# BMS-BQ76930.net
KiCad netlist of a schematic drawn in Altium Designer
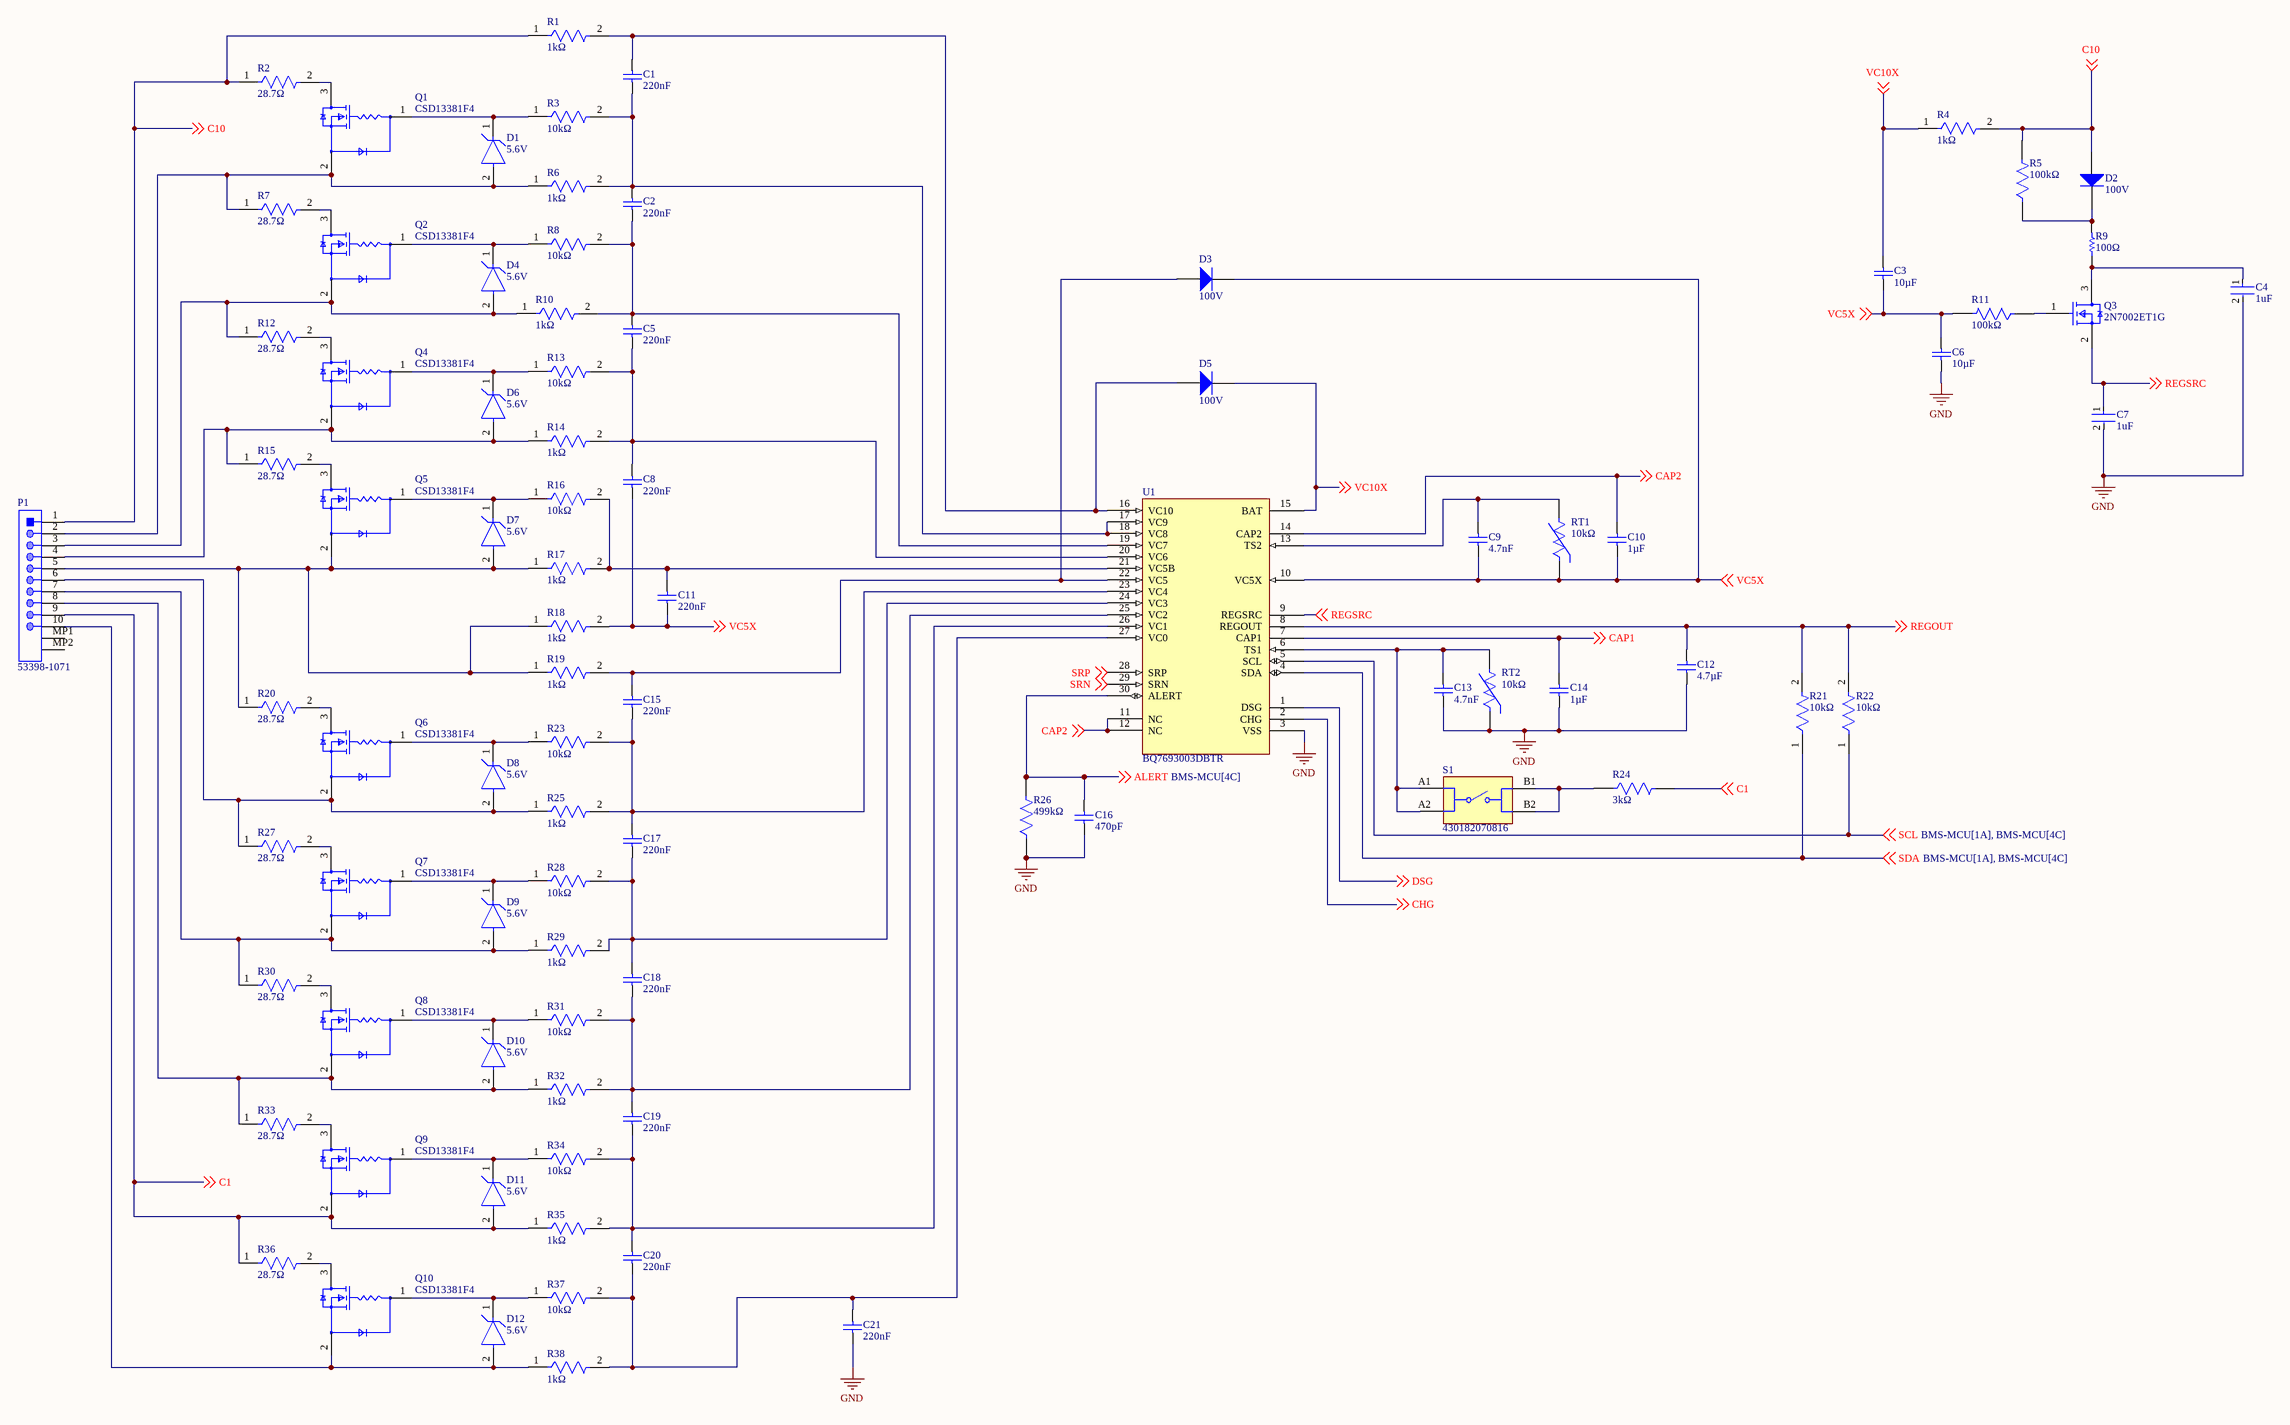
[diagram p0: BMS-BQ76930.SchDoc]

(export (version "E")
  (design (tool "Eeschema 10.0.6"))
  (components
    (comp (ref "C1")
      (value "885012206048")
      (footprint "WCAP-CSGP_0603_L1.6W0.8H0.8_Reflow")
      (description "885012206048 Ceramic Capacitor 220nF, 16VDC, 0603, ±10 %")
      (fields (field (name "TOLERANCE") "10%") (field (name "CAPACITANCE") "220nF"))
      (libsource (lib "BMS-lib") (part "CMP-03913-53914757-1"))
    )
    (comp (ref "C2")
      (value "885012206048")
      (footprint "WCAP-CSGP_0603_L1.6W0.8H0.8_Reflow")
      (description "885012206048 Ceramic Capacitor 220nF, 16VDC, 0603, ±10 %")
      (fields (field (name "TOLERANCE") "10%") (field (name "CAPACITANCE") "220nF"))
      (libsource (lib "BMS-lib") (part "CMP-03913-53914757-1"))
    )
    (comp (ref "C3")
      (value "GRM32ER7YA106KA12L")
      (footprint "CAPC3225X270X30ML30")
      (description "Chip Capacitor, 10 uF, +/- 10%, 35 V, -55 to 125 degC, 1210 (3225 Metric), RoHS, Tape and Reel")
      (fields (field (name "MANUFACTURER") "Murata") (field (name "CAPACITANCE") "10µF"))
      (libsource (lib "BMS-lib") (part "CMP-1038-02234-2"))
    )
    (comp (ref "C4")
      (value "GCJ21BR71H105KA01L")
      (footprint "FP-GCJ21B-0_3-IPC_B")
      (description "Multilayer Ceramic Capacitors MLCC - SMD/SMT 0805 1uF 10%, 50VDC,  X7R 15%")
      (fields (field (name "TOLERANCE") "10%") (field (name "CAPACITANCE") "1uF"))
      (libsource (lib "BMS-lib") (part "CMP-06035-043290-1"))
    )
    (comp (ref "C5")
      (value "885012206048")
      (footprint "WCAP-CSGP_0603_L1.6W0.8H0.8_Reflow")
      (description "885012206048 Ceramic Capacitor 220nF, 16VDC, 0603, ±10 %")
      (fields (field (name "TOLERANCE") "10%") (field (name "CAPACITANCE") "220nF"))
      (libsource (lib "BMS-lib") (part "CMP-03913-53914757-1"))
    )
    (comp (ref "C6")
      (value "GRM32ER7YA106KA12L")
      (footprint "CAPC3225X270X30ML30")
      (description "Chip Capacitor, 10 uF, +/- 10%, 35 V, -55 to 125 degC, 1210 (3225 Metric), RoHS, Tape and Reel")
      (fields (field (name "MANUFACTURER") "Murata") (field (name "CAPACITANCE") "10µF"))
      (libsource (lib "BMS-lib") (part "CMP-1038-02234-2"))
    )
    (comp (ref "C7")
      (value "GCJ21BR71H105KA01L")
      (footprint "FP-GCJ21B-0_3-IPC_B")
      (description "Multilayer Ceramic Capacitors MLCC - SMD/SMT 0805 1uF 10%, 50VDC,  X7R 15%")
      (fields (field (name "TOLERANCE") "10%") (field (name "CAPACITANCE") "1uF"))
      (libsource (lib "BMS-lib") (part "CMP-06035-043290-1"))
    )
    (comp (ref "C8")
      (value "885012206048")
      (footprint "WCAP-CSGP_0603_L1.6W0.8H0.8_Reflow")
      (description "885012206048 Ceramic Capacitor 220nF, 16VDC, 0603, ±10 %")
      (fields (field (name "TOLERANCE") "10%") (field (name "CAPACITANCE") "220nF"))
      (libsource (lib "BMS-lib") (part "CMP-03913-53914757-1"))
    )
    (comp (ref "C9")
      (value "885012206087")
      (footprint "WCAP-CSGP_0603_L1.6W0.8H0.8_Reflow")
      (description "885012206087 Cap Cer 4700PF 50V X7R 0603")
      (fields (field (name "TOLERANCE") "10%") (field (name "CAPACITANCE") "4.7nF"))
      (libsource (lib "BMS-lib") (part "CMP-03913-53914796-1"))
    )
    (comp (ref "C10")
      (value "885012206052")
      (footprint "WCAP-CSGP_0603_L1.6W0.8H0.8_Reflow")
      (fields (field (name "TOLERANCE") "10%") (field (name "CAPACITANCE") "1µF"))
      (libsource (lib "BMS-lib") (part "CMP-03913-53914761-1"))
    )
    (comp (ref "C11")
      (value "885012206048")
      (footprint "WCAP-CSGP_0603_L1.6W0.8H0.8_Reflow")
      (description "885012206048 Ceramic Capacitor 220nF, 16VDC, 0603, ±10 %")
      (fields (field (name "TOLERANCE") "10%") (field (name "CAPACITANCE") "220nF"))
      (libsource (lib "BMS-lib") (part "CMP-03913-53914757-1"))
    )
    (comp (ref "C12")
      (value "885012207025")
      (footprint "WCAP-CSGP_0805_L2W1.25H1.25")
      (fields (field (name "TOLERANCE") "10%") (field (name "CAPACITANCE") "4.7µF"))
      (libsource (lib "BMS-lib") (part "CMP-03913-65419799-1"))
    )
    (comp (ref "C13")
      (value "885012206087")
      (footprint "WCAP-CSGP_0603_L1.6W0.8H0.8_Reflow")
      (description "885012206087 Cap Cer 4700PF 50V X7R 0603")
      (fields (field (name "TOLERANCE") "10%") (field (name "CAPACITANCE") "4.7nF"))
      (libsource (lib "BMS-lib") (part "CMP-03913-53914796-1"))
    )
    (comp (ref "C14")
      (value "885012206052")
      (footprint "WCAP-CSGP_0603_L1.6W0.8H0.8_Reflow")
      (fields (field (name "TOLERANCE") "10%") (field (name "CAPACITANCE") "1µF"))
      (libsource (lib "BMS-lib") (part "CMP-03913-53914761-1"))
    )
    (comp (ref "C15")
      (value "885012206048")
      (footprint "WCAP-CSGP_0603_L1.6W0.8H0.8_Reflow")
      (description "885012206048 Ceramic Capacitor 220nF, 16VDC, 0603, ±10 %")
      (fields (field (name "TOLERANCE") "10%") (field (name "CAPACITANCE") "220nF"))
      (libsource (lib "BMS-lib") (part "CMP-03913-53914757-1"))
    )
    (comp (ref "C16")
      (value "885012206081")
      (footprint "WCAP-CSGP_0603_L1.6W0.8H0.8_Reflow")
      (description "885012206081 Cap Cer 470PF 50V X7R 0603")
      (fields (field (name "TOLERANCE") "10%") (field (name "CAPACITANCE") "470pF"))
      (libsource (lib "BMS-lib") (part "CMP-03913-53914790-1"))
    )
    (comp (ref "C17")
      (value "885012206048")
      (footprint "WCAP-CSGP_0603_L1.6W0.8H0.8_Reflow")
      (description "885012206048 Ceramic Capacitor 220nF, 16VDC, 0603, ±10 %")
      (fields (field (name "TOLERANCE") "10%") (field (name "CAPACITANCE") "220nF"))
      (libsource (lib "BMS-lib") (part "CMP-03913-53914757-1"))
    )
    (comp (ref "C18")
      (value "885012206048")
      (footprint "WCAP-CSGP_0603_L1.6W0.8H0.8_Reflow")
      (description "885012206048 Ceramic Capacitor 220nF, 16VDC, 0603, ±10 %")
      (fields (field (name "TOLERANCE") "10%") (field (name "CAPACITANCE") "220nF"))
      (libsource (lib "BMS-lib") (part "CMP-03913-53914757-1"))
    )
    (comp (ref "C19")
      (value "885012206048")
      (footprint "WCAP-CSGP_0603_L1.6W0.8H0.8_Reflow")
      (description "885012206048 Ceramic Capacitor 220nF, 16VDC, 0603, ±10 %")
      (fields (field (name "TOLERANCE") "10%") (field (name "CAPACITANCE") "220nF"))
      (libsource (lib "BMS-lib") (part "CMP-03913-53914757-1"))
    )
    (comp (ref "C20")
      (value "885012206048")
      (footprint "WCAP-CSGP_0603_L1.6W0.8H0.8_Reflow")
      (description "885012206048 Ceramic Capacitor 220nF, 16VDC, 0603, ±10 %")
      (fields (field (name "TOLERANCE") "10%") (field (name "CAPACITANCE") "220nF"))
      (libsource (lib "BMS-lib") (part "CMP-03913-53914757-1"))
    )
    (comp (ref "C21")
      (value "885012206048")
      (footprint "WCAP-CSGP_0603_L1.6W0.8H0.8_Reflow")
      (description "885012206048 Ceramic Capacitor 220nF, 16VDC, 0603, ±10 %")
      (fields (field (name "TOLERANCE") "10%") (field (name "CAPACITANCE") "220nF"))
      (libsource (lib "BMS-lib") (part "CMP-03913-53914757-1"))
    )
    (comp (ref "D1")
      (value "MM3Z5V6ST1G")
      (footprint "FP-477-02-MFG")
      (description "DIODE ZENER 5.6V 300MW SOD323")
      (fields (field (name "TOLERANCE") "2%") (field (name "VOLTAGE RATING (DC)") "5.6V"))
      (libsource (lib "BMS-lib") (part "CMP-1060-00706-2"))
    )
    (comp (ref "D2")
      (value "1N4148W-7-F")
      (footprint "DIOD-SOD123-2_V")
      (description "Fast Switching Diode, 100 V, 0.15 A, -65 to 150 degC, 2-Pin?SOD123, RoHS, Tape and Reel")
      (fields (field (name "MANUFACTURER") "DiodesIncorporated") (field (name "PEAK REVERSE VOLTAGE") "100V"))
      (libsource (lib "BMS-lib") (part "CMP-2000-04932-2"))
    )
    (comp (ref "D3")
      (value "1N4148W-7-F")
      (footprint "DIOD-SOD123-2_V")
      (description "Fast Switching Diode, 100 V, 0.15 A, -65 to 150 degC, 2-Pin?SOD123, RoHS, Tape and Reel")
      (fields (field (name "MANUFACTURER") "DiodesIncorporated") (field (name "PEAK REVERSE VOLTAGE") "100V"))
      (libsource (lib "BMS-lib") (part "CMP-2000-04932-2"))
    )
    (comp (ref "D4")
      (value "MM3Z5V6ST1G")
      (footprint "FP-477-02-MFG")
      (description "DIODE ZENER 5.6V 300MW SOD323")
      (fields (field (name "TOLERANCE") "2%") (field (name "VOLTAGE RATING (DC)") "5.6V"))
      (libsource (lib "BMS-lib") (part "CMP-1060-00706-2"))
    )
    (comp (ref "D5")
      (value "1N4148W-7-F")
      (footprint "DIOD-SOD123-2_V")
      (description "Fast Switching Diode, 100 V, 0.15 A, -65 to 150 degC, 2-Pin?SOD123, RoHS, Tape and Reel")
      (fields (field (name "MANUFACTURER") "DiodesIncorporated") (field (name "PEAK REVERSE VOLTAGE") "100V"))
      (libsource (lib "BMS-lib") (part "CMP-2000-04932-2"))
    )
    (comp (ref "D6")
      (value "MM3Z5V6ST1G")
      (footprint "FP-477-02-MFG")
      (description "DIODE ZENER 5.6V 300MW SOD323")
      (fields (field (name "TOLERANCE") "2%") (field (name "VOLTAGE RATING (DC)") "5.6V"))
      (libsource (lib "BMS-lib") (part "CMP-1060-00706-2"))
    )
    (comp (ref "D7")
      (value "MM3Z5V6ST1G")
      (footprint "FP-477-02-MFG")
      (description "DIODE ZENER 5.6V 300MW SOD323")
      (fields (field (name "TOLERANCE") "2%") (field (name "VOLTAGE RATING (DC)") "5.6V"))
      (libsource (lib "BMS-lib") (part "CMP-1060-00706-2"))
    )
    (comp (ref "D8")
      (value "MM3Z5V6ST1G")
      (footprint "FP-477-02-MFG")
      (description "DIODE ZENER 5.6V 300MW SOD323")
      (fields (field (name "TOLERANCE") "2%") (field (name "VOLTAGE RATING (DC)") "5.6V"))
      (libsource (lib "BMS-lib") (part "CMP-1060-00706-2"))
    )
    (comp (ref "D9")
      (value "MM3Z5V6ST1G")
      (footprint "FP-477-02-MFG")
      (description "DIODE ZENER 5.6V 300MW SOD323")
      (fields (field (name "TOLERANCE") "2%") (field (name "VOLTAGE RATING (DC)") "5.6V"))
      (libsource (lib "BMS-lib") (part "CMP-1060-00706-2"))
    )
    (comp (ref "D10")
      (value "MM3Z5V6ST1G")
      (footprint "FP-477-02-MFG")
      (description "DIODE ZENER 5.6V 300MW SOD323")
      (fields (field (name "TOLERANCE") "2%") (field (name "VOLTAGE RATING (DC)") "5.6V"))
      (libsource (lib "BMS-lib") (part "CMP-1060-00706-2"))
    )
    (comp (ref "D11")
      (value "MM3Z5V6ST1G")
      (footprint "FP-477-02-MFG")
      (description "DIODE ZENER 5.6V 300MW SOD323")
      (fields (field (name "TOLERANCE") "2%") (field (name "VOLTAGE RATING (DC)") "5.6V"))
      (libsource (lib "BMS-lib") (part "CMP-1060-00706-2"))
    )
    (comp (ref "D12")
      (value "MM3Z5V6ST1G")
      (footprint "FP-477-02-MFG")
      (description "DIODE ZENER 5.6V 300MW SOD323")
      (fields (field (name "TOLERANCE") "2%") (field (name "VOLTAGE RATING (DC)") "5.6V"))
      (libsource (lib "BMS-lib") (part "CMP-1060-00706-2"))
    )
    (comp (ref "P1")
      (value "53398-1071")
      (footprint "MOLX-53398-1071_V")
      (description "Male Header, Pitch 1.25 mm, 1 x 10 Position, Height 4.7 mm, -40 to 85 degC, RoHS, Tape and Reel")
      (fields (field (name "MANUFACTURER") "Molex"))
      (libsource (lib "BMS-lib") (part "CMP-2000-05635-1"))
    )
    (comp (ref "Q1")
      (value "CSD13381F4")
      (footprint "FP-CSD13381F4-MFG")
      (description "MOSFET N-CH 12V 2.1A 3PICOSTAR")
      (libsource (lib "BMS-lib") (part "CMP-04962-000059-1"))
    )
    (comp (ref "Q2")
      (value "CSD13381F4")
      (footprint "FP-CSD13381F4-MFG")
      (description "MOSFET N-CH 12V 2.1A 3PICOSTAR")
      (libsource (lib "BMS-lib") (part "CMP-04962-000059-1"))
    )
    (comp (ref "Q3")
      (value "2N7002ET1G")
      (footprint "FP-318-08-MFG")
      (description "MOSFET N-CH 60V 260MA SOT-23")
      (libsource (lib "BMS-lib") (part "CMP-1058-00769-2"))
    )
    (comp (ref "Q4")
      (value "CSD13381F4")
      (footprint "FP-CSD13381F4-MFG")
      (description "MOSFET N-CH 12V 2.1A 3PICOSTAR")
      (libsource (lib "BMS-lib") (part "CMP-04962-000059-1"))
    )
    (comp (ref "Q5")
      (value "CSD13381F4")
      (footprint "FP-CSD13381F4-MFG")
      (description "MOSFET N-CH 12V 2.1A 3PICOSTAR")
      (libsource (lib "BMS-lib") (part "CMP-04962-000059-1"))
    )
    (comp (ref "Q6")
      (value "CSD13381F4")
      (footprint "FP-CSD13381F4-MFG")
      (description "MOSFET N-CH 12V 2.1A 3PICOSTAR")
      (libsource (lib "BMS-lib") (part "CMP-04962-000059-1"))
    )
    (comp (ref "Q7")
      (value "CSD13381F4")
      (footprint "FP-CSD13381F4-MFG")
      (description "MOSFET N-CH 12V 2.1A 3PICOSTAR")
      (libsource (lib "BMS-lib") (part "CMP-04962-000059-1"))
    )
    (comp (ref "Q8")
      (value "CSD13381F4")
      (footprint "FP-CSD13381F4-MFG")
      (description "MOSFET N-CH 12V 2.1A 3PICOSTAR")
      (libsource (lib "BMS-lib") (part "CMP-04962-000059-1"))
    )
    (comp (ref "Q9")
      (value "CSD13381F4")
      (footprint "FP-CSD13381F4-MFG")
      (description "MOSFET N-CH 12V 2.1A 3PICOSTAR")
      (libsource (lib "BMS-lib") (part "CMP-04962-000059-1"))
    )
    (comp (ref "Q10")
      (value "CSD13381F4")
      (footprint "FP-CSD13381F4-MFG")
      (description "MOSFET N-CH 12V 2.1A 3PICOSTAR")
      (libsource (lib "BMS-lib") (part "CMP-04962-000059-1"))
    )
    (comp (ref "R1")
      (value "CRCW06031K00JNEA")
      (footprint "FP-CRCW0603-e3-MFG")
      (description "RES Thick Film, 1kΩ, 5%, 0.1W, 200ppm/°C, 0603")
      (fields (field (name "TOLERANCE") "5%") (field (name "RESISTANCE") "1kΩ"))
      (libsource (lib "BMS-lib") (part "CMP-02407-007100-1"))
    )
    (comp (ref "R2")
      (value "28.7Ω")
      (fields
        (field (name "MANUFACTURER") "Vishay Dale")
        (field (name "MANUFACTURER PART NUMBER") "CRCW201028R7FKEF")
        (field (name "TOLERANCE") "1%")
      )
      (libsource (lib "BMS-lib") (part "CRCW201028R7FKEF"))
    )
    (comp (ref "R3")
      (value "CRCW060310K0JNEA")
      (footprint "FP-CRCW0603-e3-MFG")
      (description "RES Thick Film, 10kΩ, 5%, 0.1W, 200ppm/°C, 0603")
      (fields (field (name "TOLERANCE") "5%") (field (name "RESISTANCE") "10kΩ"))
      (libsource (lib "BMS-lib") (part "CMP-2000-03838-2"))
    )
    (comp (ref "R4")
      (value "CRCW06031K00JNEA")
      (footprint "FP-CRCW0603-e3-MFG")
      (description "RES Thick Film, 1kΩ, 5%, 0.1W, 200ppm/°C, 0603")
      (fields (field (name "TOLERANCE") "5%") (field (name "RESISTANCE") "1kΩ"))
      (libsource (lib "BMS-lib") (part "CMP-02407-007100-1"))
    )
    (comp (ref "R5")
      (value "CRCW0805100KFKEA")
      (footprint "FP-CRCW0805-e3-MFG")
      (description "RES Thick Film, 100kΩ, 1%, 0.125W, 100ppm/°C, 0805")
      (fields (field (name "TOLERANCE") "1%") (field (name "RESISTANCE") "100kΩ"))
      (libsource (lib "BMS-lib") (part "CMP-2001-04899-2"))
    )
    (comp (ref "R6")
      (value "CRCW06031K00JNEA")
      (footprint "FP-CRCW0603-e3-MFG")
      (description "RES Thick Film, 1kΩ, 5%, 0.1W, 200ppm/°C, 0603")
      (fields (field (name "TOLERANCE") "5%") (field (name "RESISTANCE") "1kΩ"))
      (libsource (lib "BMS-lib") (part "CMP-02407-007100-1"))
    )
    (comp (ref "R7")
      (value "28.7Ω")
      (fields
        (field (name "MANUFACTURER") "Vishay Dale")
        (field (name "MANUFACTURER PART NUMBER") "CRCW201028R7FKEF")
        (field (name "TOLERANCE") "1%")
      )
      (libsource (lib "BMS-lib") (part "CRCW201028R7FKEF"))
    )
    (comp (ref "R8")
      (value "CRCW060310K0JNEA")
      (footprint "FP-CRCW0603-e3-MFG")
      (description "RES Thick Film, 10kΩ, 5%, 0.1W, 200ppm/°C, 0603")
      (fields (field (name "TOLERANCE") "5%") (field (name "RESISTANCE") "10kΩ"))
      (libsource (lib "BMS-lib") (part "CMP-2000-03838-2"))
    )
    (comp (ref "R9")
      (value "CRCW0805100RFKEA")
      (footprint "RESC2013X50X30ML20T20")
      (fields (field (name "MANUFACTURER") "Vishay Dale") (field (name "RESISTANCE") "100Ω"))
      (libsource (lib "BMS-lib") (part "CMP-2001-04901-1"))
    )
    (comp (ref "R10")
      (value "CRCW06031K00JNEA")
      (footprint "FP-CRCW0603-e3-MFG")
      (description "RES Thick Film, 1kΩ, 5%, 0.1W, 200ppm/°C, 0603")
      (fields (field (name "TOLERANCE") "5%") (field (name "RESISTANCE") "1kΩ"))
      (libsource (lib "BMS-lib") (part "CMP-02407-007100-1"))
    )
    (comp (ref "R11")
      (value "CRCW0805100KFKEA")
      (footprint "FP-CRCW0805-e3-MFG")
      (description "RES Thick Film, 100kΩ, 1%, 0.125W, 100ppm/°C, 0805")
      (fields (field (name "TOLERANCE") "1%") (field (name "RESISTANCE") "100kΩ"))
      (libsource (lib "BMS-lib") (part "CMP-2001-04899-2"))
    )
    (comp (ref "R12")
      (value "28.7Ω")
      (fields
        (field (name "MANUFACTURER") "Vishay Dale")
        (field (name "MANUFACTURER PART NUMBER") "CRCW201028R7FKEF")
        (field (name "TOLERANCE") "1%")
      )
      (libsource (lib "BMS-lib") (part "CRCW201028R7FKEF"))
    )
    (comp (ref "R13")
      (value "CRCW060310K0JNEA")
      (footprint "FP-CRCW0603-e3-MFG")
      (description "RES Thick Film, 10kΩ, 5%, 0.1W, 200ppm/°C, 0603")
      (fields (field (name "TOLERANCE") "5%") (field (name "RESISTANCE") "10kΩ"))
      (libsource (lib "BMS-lib") (part "CMP-2000-03838-2"))
    )
    (comp (ref "R14")
      (value "CRCW06031K00JNEA")
      (footprint "FP-CRCW0603-e3-MFG")
      (description "RES Thick Film, 1kΩ, 5%, 0.1W, 200ppm/°C, 0603")
      (fields (field (name "TOLERANCE") "5%") (field (name "RESISTANCE") "1kΩ"))
      (libsource (lib "BMS-lib") (part "CMP-02407-007100-1"))
    )
    (comp (ref "R15")
      (value "28.7Ω")
      (fields
        (field (name "MANUFACTURER") "Vishay Dale")
        (field (name "MANUFACTURER PART NUMBER") "CRCW201028R7FKEF")
        (field (name "TOLERANCE") "1%")
      )
      (libsource (lib "BMS-lib") (part "CRCW201028R7FKEF"))
    )
    (comp (ref "R16")
      (value "CRCW060310K0JNEA")
      (footprint "FP-CRCW0603-e3-MFG")
      (description "RES Thick Film, 10kΩ, 5%, 0.1W, 200ppm/°C, 0603")
      (fields (field (name "TOLERANCE") "5%") (field (name "RESISTANCE") "10kΩ"))
      (libsource (lib "BMS-lib") (part "CMP-2000-03838-2"))
    )
    (comp (ref "R17")
      (value "CRCW06031K00JNEA")
      (footprint "FP-CRCW0603-e3-MFG")
      (description "RES Thick Film, 1kΩ, 5%, 0.1W, 200ppm/°C, 0603")
      (fields (field (name "TOLERANCE") "5%") (field (name "RESISTANCE") "1kΩ"))
      (libsource (lib "BMS-lib") (part "CMP-02407-007100-1"))
    )
    (comp (ref "R18")
      (value "CRCW06031K00JNEA")
      (footprint "FP-CRCW0603-e3-MFG")
      (description "RES Thick Film, 1kΩ, 5%, 0.1W, 200ppm/°C, 0603")
      (fields (field (name "TOLERANCE") "5%") (field (name "RESISTANCE") "1kΩ"))
      (libsource (lib "BMS-lib") (part "CMP-02407-007100-1"))
    )
    (comp (ref "R19")
      (value "CRCW06031K00JNEA")
      (footprint "FP-CRCW0603-e3-MFG")
      (description "RES Thick Film, 1kΩ, 5%, 0.1W, 200ppm/°C, 0603")
      (fields (field (name "TOLERANCE") "5%") (field (name "RESISTANCE") "1kΩ"))
      (libsource (lib "BMS-lib") (part "CMP-02407-007100-1"))
    )
    (comp (ref "R20")
      (value "28.7Ω")
      (fields
        (field (name "MANUFACTURER") "Vishay Dale")
        (field (name "MANUFACTURER PART NUMBER") "CRCW201028R7FKEF")
        (field (name "TOLERANCE") "1%")
      )
      (libsource (lib "BMS-lib") (part "CRCW201028R7FKEF"))
    )
    (comp (ref "R21")
      (value "CRCW060310K0JNEA")
      (footprint "FP-CRCW0603-e3-MFG")
      (description "RES Thick Film, 10kΩ, 5%, 0.1W, 200ppm/°C, 0603")
      (fields (field (name "TOLERANCE") "5%") (field (name "RESISTANCE") "10kΩ"))
      (libsource (lib "BMS-lib") (part "CMP-2000-03838-2"))
    )
    (comp (ref "R22")
      (value "CRCW060310K0JNEA")
      (footprint "FP-CRCW0603-e3-MFG")
      (description "RES Thick Film, 10kΩ, 5%, 0.1W, 200ppm/°C, 0603")
      (fields (field (name "TOLERANCE") "5%") (field (name "RESISTANCE") "10kΩ"))
      (libsource (lib "BMS-lib") (part "CMP-2000-03838-2"))
    )
    (comp (ref "R23")
      (value "CRCW060310K0JNEA")
      (footprint "FP-CRCW0603-e3-MFG")
      (description "RES Thick Film, 10kΩ, 5%, 0.1W, 200ppm/°C, 0603")
      (fields (field (name "TOLERANCE") "5%") (field (name "RESISTANCE") "10kΩ"))
      (libsource (lib "BMS-lib") (part "CMP-2000-03838-2"))
    )
    (comp (ref "R24")
      (value "CRCW06033K00JNEA")
      (footprint "FP-CRCW0603-e3-MFG")
      (description "RES Thick Film, 3kΩ, 5%, 0.1W, 200ppm/°C, 0603")
      (fields (field (name "TOLERANCE") "5%") (field (name "RESISTANCE") "3kΩ"))
      (libsource (lib "BMS-lib") (part "CMP-2000-03294-2"))
    )
    (comp (ref "R25")
      (value "CRCW06031K00JNEA")
      (footprint "FP-CRCW0603-e3-MFG")
      (description "RES Thick Film, 1kΩ, 5%, 0.1W, 200ppm/°C, 0603")
      (fields (field (name "TOLERANCE") "5%") (field (name "RESISTANCE") "1kΩ"))
      (libsource (lib "BMS-lib") (part "CMP-02407-007100-1"))
    )
    (comp (ref "R26")
      (value "CRCW0603499KFKEA")
      (footprint "FP-CRCW0603-e3-MFG")
      (fields
        (field (name "TOLERANCE") "1%")
        (field (name "RESISTANCE") "499kΩ")
        (field (name "MANUFACTURER") "Vishay")
        (field (name "POWER") "100mW")
      )
      (libsource (lib "BMS-lib") (part "CMP-2000-03389-2"))
    )
    (comp (ref "R27")
      (value "28.7Ω")
      (fields
        (field (name "MANUFACTURER") "Vishay Dale")
        (field (name "MANUFACTURER PART NUMBER") "CRCW201028R7FKEF")
        (field (name "TOLERANCE") "1%")
      )
      (libsource (lib "BMS-lib") (part "CRCW201028R7FKEF"))
    )
    (comp (ref "R28")
      (value "CRCW060310K0JNEA")
      (footprint "FP-CRCW0603-e3-MFG")
      (description "RES Thick Film, 10kΩ, 5%, 0.1W, 200ppm/°C, 0603")
      (fields (field (name "TOLERANCE") "5%") (field (name "RESISTANCE") "10kΩ"))
      (libsource (lib "BMS-lib") (part "CMP-2000-03838-2"))
    )
    (comp (ref "R29")
      (value "CRCW06031K00JNEA")
      (footprint "FP-CRCW0603-e3-MFG")
      (description "RES Thick Film, 1kΩ, 5%, 0.1W, 200ppm/°C, 0603")
      (fields (field (name "TOLERANCE") "5%") (field (name "RESISTANCE") "1kΩ"))
      (libsource (lib "BMS-lib") (part "CMP-02407-007100-1"))
    )
    (comp (ref "R30")
      (value "28.7Ω")
      (fields
        (field (name "MANUFACTURER") "Vishay Dale")
        (field (name "MANUFACTURER PART NUMBER") "CRCW201028R7FKEF")
        (field (name "TOLERANCE") "1%")
      )
      (libsource (lib "BMS-lib") (part "CRCW201028R7FKEF"))
    )
    (comp (ref "R31")
      (value "CRCW060310K0JNEA")
      (footprint "FP-CRCW0603-e3-MFG")
      (description "RES Thick Film, 10kΩ, 5%, 0.1W, 200ppm/°C, 0603")
      (fields (field (name "TOLERANCE") "5%") (field (name "RESISTANCE") "10kΩ"))
      (libsource (lib "BMS-lib") (part "CMP-2000-03838-2"))
    )
    (comp (ref "R32")
      (value "CRCW06031K00JNEA")
      (footprint "FP-CRCW0603-e3-MFG")
      (description "RES Thick Film, 1kΩ, 5%, 0.1W, 200ppm/°C, 0603")
      (fields (field (name "TOLERANCE") "5%") (field (name "RESISTANCE") "1kΩ"))
      (libsource (lib "BMS-lib") (part "CMP-02407-007100-1"))
    )
    (comp (ref "R33")
      (value "28.7Ω")
      (fields
        (field (name "MANUFACTURER") "Vishay Dale")
        (field (name "MANUFACTURER PART NUMBER") "CRCW201028R7FKEF")
        (field (name "TOLERANCE") "1%")
      )
      (libsource (lib "BMS-lib") (part "CRCW201028R7FKEF"))
    )
    (comp (ref "R34")
      (value "CRCW060310K0JNEA")
      (footprint "FP-CRCW0603-e3-MFG")
      (description "RES Thick Film, 10kΩ, 5%, 0.1W, 200ppm/°C, 0603")
      (fields (field (name "TOLERANCE") "5%") (field (name "RESISTANCE") "10kΩ"))
      (libsource (lib "BMS-lib") (part "CMP-2000-03838-2"))
    )
    (comp (ref "R35")
      (value "CRCW06031K00JNEA")
      (footprint "FP-CRCW0603-e3-MFG")
      (description "RES Thick Film, 1kΩ, 5%, 0.1W, 200ppm/°C, 0603")
      (fields (field (name "TOLERANCE") "5%") (field (name "RESISTANCE") "1kΩ"))
      (libsource (lib "BMS-lib") (part "CMP-02407-007100-1"))
    )
    (comp (ref "R36")
      (value "28.7Ω")
      (fields
        (field (name "MANUFACTURER") "Vishay Dale")
        (field (name "MANUFACTURER PART NUMBER") "CRCW201028R7FKEF")
        (field (name "TOLERANCE") "1%")
      )
      (libsource (lib "BMS-lib") (part "CRCW201028R7FKEF"))
    )
    (comp (ref "R37")
      (value "CRCW060310K0JNEA")
      (footprint "FP-CRCW0603-e3-MFG")
      (description "RES Thick Film, 10kΩ, 5%, 0.1W, 200ppm/°C, 0603")
      (fields (field (name "TOLERANCE") "5%") (field (name "RESISTANCE") "10kΩ"))
      (libsource (lib "BMS-lib") (part "CMP-2000-03838-2"))
    )
    (comp (ref "R38")
      (value "CRCW06031K00JNEA")
      (footprint "FP-CRCW0603-e3-MFG")
      (description "RES Thick Film, 1kΩ, 5%, 0.1W, 200ppm/°C, 0603")
      (fields (field (name "TOLERANCE") "5%") (field (name "RESISTANCE") "1kΩ"))
      (libsource (lib "BMS-lib") (part "CMP-02407-007100-1"))
    )
    (comp (ref "RT1")
      (value "103AT-2")
      (footprint "FP-103AT-2-MFG")
      (description "Thermistor NTC 10KOhm 1% 2-Pin")
      (fields (field (name "TOLERANCE") "1%") (field (name "RESISTANCE") "10kΩ"))
      (libsource (lib "BMS-lib") (part "CMP-2000-05824-2"))
    )
    (comp (ref "RT2")
      (value "103AT-2")
      (footprint "FP-103AT-2-MFG")
      (description "Thermistor NTC 10KOhm 1% 2-Pin")
      (fields (field (name "TOLERANCE") "1%") (field (name "RESISTANCE") "10kΩ"))
      (libsource (lib "BMS-lib") (part "CMP-2000-05824-2"))
    )
    (comp (ref "S1")
      (value "430182070816")
      (footprint "430182070816")
      (description "Switch Tactile Spst-no 0.05A 12V")
      (libsource (lib "BMS-lib") (part "CMP-1452-00015-3"))
    )
    (comp (ref "U1")
      (value "BQ7693003DBTR")
      (footprint "FP-DBT0030A-IPC_C")
      (description "IC BATT MGMT LI-ION AFE 30TSSOP")
      (fields
        (field (name "OCTOPART") "https://octopart.com/bq7693003dbtr-texas+instruments-34472212")
        (field (name "MANUFACTURER") "Texas Instruments")
      )
      (libsource (lib "BMS-lib") (part "CMP-04911-000006-1"))
    )
  )
  (nets
    (net (code "1") (name "ALERT") (class "Default")
      (node (ref "C16") (pin "2") (pinfunction "2_2") (pintype "passive"))
      (node (ref "R26") (pin "2") (pinfunction "2_2") (pintype "passive"))
      (node (ref "U1") (pin "30") (pinfunction "ALERT_30") (pintype "bidirectional"))
    )
    (net (code "2") (name "C1") (class "Default")
      (node (ref "D11") (pin "2") (pinfunction "A_2") (pintype "passive"))
      (node (ref "P1") (pin "9") (pinfunction "9_9") (pintype "passive"))
      (node (ref "Q9") (pin "2") (pinfunction "S_2") (pintype "passive"))
      (node (ref "R24") (pin "2") (pinfunction "2_2") (pintype "passive"))
      (node (ref "R35") (pin "1") (pinfunction "1_1") (pintype "passive"))
      (node (ref "R36") (pin "1") (pinfunction "1_1") (pintype "passive"))
    )
    (net (code "3") (name "C10") (class "Default")
      (node (ref "D2") (pin "1") (pinfunction "A_1") (pintype "passive"))
      (node (ref "P1") (pin "1") (pinfunction "1_1") (pintype "passive"))
      (node (ref "R1") (pin "1") (pinfunction "1_1") (pintype "passive"))
      (node (ref "R2") (pin "1") (pinfunction "1_1") (pintype "passive"))
      (node (ref "R4") (pin "2") (pinfunction "2_2") (pintype "passive"))
      (node (ref "R5") (pin "2") (pinfunction "2_2") (pintype "passive"))
    )
    (net (code "4") (name "CAP1") (class "Default")
      (node (ref "C14") (pin "2") (pinfunction "2_2") (pintype "passive"))
      (node (ref "U1") (pin "7") (pinfunction "CAP1_7") (pintype "passive"))
    )
    (net (code "5") (name "CAP2") (class "Default")
      (node (ref "C10") (pin "2") (pinfunction "2_2") (pintype "passive"))
      (node (ref "U1") (pin "11") (pinfunction "NC_11") (pintype "passive"))
      (node (ref "U1") (pin "12") (pinfunction "NC_12") (pintype "passive"))
      (node (ref "U1") (pin "14") (pinfunction "CAP2_14") (pintype "passive"))
    )
    (net (code "6") (name "CHG") (class "Default")
      (node (ref "U1") (pin "2") (pinfunction "CHG_2") (pintype "passive"))
    )
    (net (code "7") (name "DSG") (class "Default")
      (node (ref "U1") (pin "1") (pinfunction "DSG_1") (pintype "passive"))
    )
    (net (code "8") (name "GND") (class "Default")
      (node (ref "C12") (pin "1") (pinfunction "1_1") (pintype "passive"))
      (node (ref "C13") (pin "1") (pinfunction "1_1") (pintype "passive"))
      (node (ref "C14") (pin "1") (pinfunction "1_1") (pintype "passive"))
      (node (ref "C16") (pin "1") (pinfunction "1_1") (pintype "passive"))
      (node (ref "C21") (pin "1") (pinfunction "1_1") (pintype "passive"))
      (node (ref "C4") (pin "2") (pinfunction "2_2") (pintype "passive"))
      (node (ref "C6") (pin "1") (pinfunction "1_1") (pintype "passive"))
      (node (ref "C7") (pin "2") (pinfunction "2_2") (pintype "passive"))
      (node (ref "R26") (pin "1") (pinfunction "1_1") (pintype "passive"))
      (node (ref "RT2") (pin "1") (pinfunction "1_1") (pintype "passive"))
      (node (ref "U1") (pin "3") (pinfunction "VSS_3") (pintype "passive"))
    )
    (net (code "9") (name "Net-(D1-A)") (class "Default")
      (node (ref "D1") (pin "2") (pinfunction "A_2") (pintype "passive"))
      (node (ref "P1") (pin "2") (pinfunction "2_2") (pintype "passive"))
      (node (ref "Q1") (pin "2") (pinfunction "S_2") (pintype "passive"))
      (node (ref "R6") (pin "1") (pinfunction "1_1") (pintype "passive"))
      (node (ref "R7") (pin "1") (pinfunction "1_1") (pintype "passive"))
    )
    (net (code "10") (name "Net-(D1-C)") (class "Default")
      (node (ref "D1") (pin "1") (pinfunction "C_1") (pintype "passive"))
      (node (ref "Q1") (pin "1") (pinfunction "G_1") (pintype "passive"))
      (node (ref "R3") (pin "1") (pinfunction "1_1") (pintype "passive"))
    )
    (net (code "11") (name "Net-(D2-K)") (class "Default")
      (node (ref "D2") (pin "2") (pinfunction "K_2") (pintype "passive"))
      (node (ref "R5") (pin "1") (pinfunction "1_1") (pintype "passive"))
      (node (ref "R9") (pin "2") (pinfunction "2_2") (pintype "passive"))
    )
    (net (code "12") (name "Net-(D3-A)") (class "Default")
      (node (ref "C15") (pin "2") (pinfunction "2_2") (pintype "passive"))
      (node (ref "D3") (pin "1") (pinfunction "A_1") (pintype "passive"))
      (node (ref "R19") (pin "2") (pinfunction "2_2") (pintype "passive"))
      (node (ref "U1") (pin "22") (pinfunction "VC5_22") (pintype "input"))
    )
    (net (code "13") (name "Net-(D4-A)") (class "Default")
      (node (ref "D4") (pin "2") (pinfunction "A_2") (pintype "passive"))
      (node (ref "P1") (pin "3") (pinfunction "3_3") (pintype "passive"))
      (node (ref "Q2") (pin "2") (pinfunction "S_2") (pintype "passive"))
      (node (ref "R10") (pin "1") (pinfunction "1_1") (pintype "passive"))
      (node (ref "R12") (pin "1") (pinfunction "1_1") (pintype "passive"))
    )
    (net (code "14") (name "Net-(D4-C)") (class "Default")
      (node (ref "D4") (pin "1") (pinfunction "C_1") (pintype "passive"))
      (node (ref "Q2") (pin "1") (pinfunction "G_1") (pintype "passive"))
      (node (ref "R8") (pin "1") (pinfunction "1_1") (pintype "passive"))
    )
    (net (code "15") (name "Net-(D5-A)") (class "Default")
      (node (ref "C1") (pin "2") (pinfunction "2_2") (pintype "passive"))
      (node (ref "D5") (pin "1") (pinfunction "A_1") (pintype "passive"))
      (node (ref "R1") (pin "2") (pinfunction "2_2") (pintype "passive"))
      (node (ref "U1") (pin "16") (pinfunction "VC10_16") (pintype "input"))
    )
    (net (code "16") (name "Net-(D6-A)") (class "Default")
      (node (ref "D6") (pin "2") (pinfunction "A_2") (pintype "passive"))
      (node (ref "P1") (pin "4") (pinfunction "4_4") (pintype "passive"))
      (node (ref "Q4") (pin "2") (pinfunction "S_2") (pintype "passive"))
      (node (ref "R14") (pin "1") (pinfunction "1_1") (pintype "passive"))
      (node (ref "R15") (pin "1") (pinfunction "1_1") (pintype "passive"))
    )
    (net (code "17") (name "Net-(D6-C)") (class "Default")
      (node (ref "D6") (pin "1") (pinfunction "C_1") (pintype "passive"))
      (node (ref "Q4") (pin "1") (pinfunction "G_1") (pintype "passive"))
      (node (ref "R13") (pin "1") (pinfunction "1_1") (pintype "passive"))
    )
    (net (code "18") (name "Net-(D7-A)") (class "Default")
      (node (ref "D7") (pin "2") (pinfunction "A_2") (pintype "passive"))
      (node (ref "P1") (pin "5") (pinfunction "5_5") (pintype "passive"))
      (node (ref "Q5") (pin "2") (pinfunction "S_2") (pintype "passive"))
      (node (ref "R17") (pin "1") (pinfunction "1_1") (pintype "passive"))
      (node (ref "R18") (pin "1") (pinfunction "1_1") (pintype "passive"))
      (node (ref "R19") (pin "1") (pinfunction "1_1") (pintype "passive"))
      (node (ref "R20") (pin "1") (pinfunction "1_1") (pintype "passive"))
    )
    (net (code "19") (name "Net-(D7-C)") (class "Default")
      (node (ref "D7") (pin "1") (pinfunction "C_1") (pintype "passive"))
      (node (ref "Q5") (pin "1") (pinfunction "G_1") (pintype "passive"))
      (node (ref "R16") (pin "1") (pinfunction "1_1") (pintype "passive"))
    )
    (net (code "20") (name "Net-(D8-A)") (class "Default")
      (node (ref "D8") (pin "2") (pinfunction "A_2") (pintype "passive"))
      (node (ref "P1") (pin "6") (pinfunction "6_6") (pintype "passive"))
      (node (ref "Q6") (pin "2") (pinfunction "S_2") (pintype "passive"))
      (node (ref "R25") (pin "1") (pinfunction "1_1") (pintype "passive"))
      (node (ref "R27") (pin "1") (pinfunction "1_1") (pintype "passive"))
    )
    (net (code "21") (name "Net-(D8-C)") (class "Default")
      (node (ref "D8") (pin "1") (pinfunction "C_1") (pintype "passive"))
      (node (ref "Q6") (pin "1") (pinfunction "G_1") (pintype "passive"))
      (node (ref "R23") (pin "1") (pinfunction "1_1") (pintype "passive"))
    )
    (net (code "22") (name "Net-(D9-A)") (class "Default")
      (node (ref "D9") (pin "2") (pinfunction "A_2") (pintype "passive"))
      (node (ref "P1") (pin "7") (pinfunction "7_7") (pintype "passive"))
      (node (ref "Q7") (pin "2") (pinfunction "S_2") (pintype "passive"))
      (node (ref "R29") (pin "1") (pinfunction "1_1") (pintype "passive"))
      (node (ref "R30") (pin "1") (pinfunction "1_1") (pintype "passive"))
    )
    (net (code "23") (name "Net-(D9-C)") (class "Default")
      (node (ref "D9") (pin "1") (pinfunction "C_1") (pintype "passive"))
      (node (ref "Q7") (pin "1") (pinfunction "G_1") (pintype "passive"))
      (node (ref "R28") (pin "1") (pinfunction "1_1") (pintype "passive"))
    )
    (net (code "24") (name "Net-(D10-A)") (class "Default")
      (node (ref "D10") (pin "2") (pinfunction "A_2") (pintype "passive"))
      (node (ref "P1") (pin "8") (pinfunction "8_8") (pintype "passive"))
      (node (ref "Q8") (pin "2") (pinfunction "S_2") (pintype "passive"))
      (node (ref "R32") (pin "1") (pinfunction "1_1") (pintype "passive"))
      (node (ref "R33") (pin "1") (pinfunction "1_1") (pintype "passive"))
    )
    (net (code "25") (name "Net-(D10-C)") (class "Default")
      (node (ref "D10") (pin "1") (pinfunction "C_1") (pintype "passive"))
      (node (ref "Q8") (pin "1") (pinfunction "G_1") (pintype "passive"))
      (node (ref "R31") (pin "1") (pinfunction "1_1") (pintype "passive"))
    )
    (net (code "26") (name "Net-(D11-C)") (class "Default")
      (node (ref "D11") (pin "1") (pinfunction "C_1") (pintype "passive"))
      (node (ref "Q9") (pin "1") (pinfunction "G_1") (pintype "passive"))
      (node (ref "R34") (pin "1") (pinfunction "1_1") (pintype "passive"))
    )
    (net (code "27") (name "Net-(D12-A)") (class "Default")
      (node (ref "D12") (pin "2") (pinfunction "A_2") (pintype "passive"))
      (node (ref "P1") (pin "10") (pinfunction "10_10") (pintype "passive"))
      (node (ref "Q10") (pin "2") (pinfunction "S_2") (pintype "passive"))
      (node (ref "R38") (pin "1") (pinfunction "1_1") (pintype "passive"))
    )
    (net (code "28") (name "Net-(D12-C)") (class "Default")
      (node (ref "D12") (pin "1") (pinfunction "C_1") (pintype "passive"))
      (node (ref "Q10") (pin "1") (pinfunction "G_1") (pintype "passive"))
      (node (ref "R37") (pin "1") (pinfunction "1_1") (pintype "passive"))
    )
    (net (code "29") (name "Net-(Q1-D)") (class "Default")
      (node (ref "Q1") (pin "3") (pinfunction "D_3") (pintype "passive"))
      (node (ref "R2") (pin "2") (pinfunction "2_2") (pintype "passive"))
    )
    (net (code "30") (name "Net-(Q2-D)") (class "Default")
      (node (ref "Q2") (pin "3") (pinfunction "D_3") (pintype "passive"))
      (node (ref "R7") (pin "2") (pinfunction "2_2") (pintype "passive"))
    )
    (net (code "31") (name "Net-(Q3-Drain)") (class "Default")
      (node (ref "C4") (pin "1") (pinfunction "1_1") (pintype "passive"))
      (node (ref "Q3") (pin "3") (pinfunction "Drain_3") (pintype "passive"))
      (node (ref "R9") (pin "1") (pinfunction "1_1") (pintype "passive"))
    )
    (net (code "32") (name "Net-(Q3-Gate)") (class "Default")
      (node (ref "Q3") (pin "1") (pinfunction "Gate_1") (pintype "passive"))
      (node (ref "R11") (pin "1") (pinfunction "1_1") (pintype "passive"))
    )
    (net (code "33") (name "Net-(Q4-D)") (class "Default")
      (node (ref "Q4") (pin "3") (pinfunction "D_3") (pintype "passive"))
      (node (ref "R12") (pin "2") (pinfunction "2_2") (pintype "passive"))
    )
    (net (code "34") (name "Net-(Q5-D)") (class "Default")
      (node (ref "Q5") (pin "3") (pinfunction "D_3") (pintype "passive"))
      (node (ref "R15") (pin "2") (pinfunction "2_2") (pintype "passive"))
    )
    (net (code "35") (name "Net-(Q6-D)") (class "Default")
      (node (ref "Q6") (pin "3") (pinfunction "D_3") (pintype "passive"))
      (node (ref "R20") (pin "2") (pinfunction "2_2") (pintype "passive"))
    )
    (net (code "36") (name "Net-(Q7-D)") (class "Default")
      (node (ref "Q7") (pin "3") (pinfunction "D_3") (pintype "passive"))
      (node (ref "R27") (pin "2") (pinfunction "2_2") (pintype "passive"))
    )
    (net (code "37") (name "Net-(Q8-D)") (class "Default")
      (node (ref "Q8") (pin "3") (pinfunction "D_3") (pintype "passive"))
      (node (ref "R30") (pin "2") (pinfunction "2_2") (pintype "passive"))
    )
    (net (code "38") (name "Net-(Q9-D)") (class "Default")
      (node (ref "Q9") (pin "3") (pinfunction "D_3") (pintype "passive"))
      (node (ref "R33") (pin "2") (pinfunction "2_2") (pintype "passive"))
    )
    (net (code "39") (name "Net-(Q10-D)") (class "Default")
      (node (ref "Q10") (pin "3") (pinfunction "D_3") (pintype "passive"))
      (node (ref "R36") (pin "2") (pinfunction "2_2") (pintype "passive"))
    )
    (net (code "40") (name "Net-(R24-Pad1)") (class "Default")
      (node (ref "R24") (pin "1") (pinfunction "1_1") (pintype "passive"))
      (node (ref "S1") (pin "B1") (pinfunction "B1_B1") (pintype "passive"))
      (node (ref "S1") (pin "B2") (pinfunction "B2_B2") (pintype "passive"))
    )
    (net (code "41") (name "Net-(U1-TS1)") (class "Default")
      (node (ref "C13") (pin "2") (pinfunction "2_2") (pintype "passive"))
      (node (ref "RT2") (pin "2") (pinfunction "2_2") (pintype "passive"))
      (node (ref "S1") (pin "A1") (pinfunction "A1_A1") (pintype "passive"))
      (node (ref "S1") (pin "A2") (pinfunction "A2_A2") (pintype "passive"))
      (node (ref "U1") (pin "6") (pinfunction "TS1_6") (pintype "input"))
    )
    (net (code "42") (name "Net-(U1-TS2)") (class "Default")
      (node (ref "C9") (pin "2") (pinfunction "2_2") (pintype "passive"))
      (node (ref "RT1") (pin "2") (pinfunction "2_2") (pintype "passive"))
      (node (ref "U1") (pin "13") (pinfunction "TS2_13") (pintype "input"))
    )
    (net (code "43") (name "Net-(U1-VC0)") (class "Default")
      (node (ref "C20") (pin "1") (pinfunction "1_1") (pintype "passive"))
      (node (ref "C21") (pin "2") (pinfunction "2_2") (pintype "passive"))
      (node (ref "R37") (pin "2") (pinfunction "2_2") (pintype "passive"))
      (node (ref "R38") (pin "2") (pinfunction "2_2") (pintype "passive"))
      (node (ref "U1") (pin "27") (pinfunction "VC0_27") (pintype "input"))
    )
    (net (code "44") (name "Net-(U1-VC1)") (class "Default")
      (node (ref "C19") (pin "1") (pinfunction "1_1") (pintype "passive"))
      (node (ref "C20") (pin "2") (pinfunction "2_2") (pintype "passive"))
      (node (ref "R34") (pin "2") (pinfunction "2_2") (pintype "passive"))
      (node (ref "R35") (pin "2") (pinfunction "2_2") (pintype "passive"))
      (node (ref "U1") (pin "26") (pinfunction "VC1_26") (pintype "input"))
    )
    (net (code "45") (name "Net-(U1-VC2)") (class "Default")
      (node (ref "C18") (pin "1") (pinfunction "1_1") (pintype "passive"))
      (node (ref "C19") (pin "2") (pinfunction "2_2") (pintype "passive"))
      (node (ref "R31") (pin "2") (pinfunction "2_2") (pintype "passive"))
      (node (ref "R32") (pin "2") (pinfunction "2_2") (pintype "passive"))
      (node (ref "U1") (pin "25") (pinfunction "VC2_25") (pintype "input"))
    )
    (net (code "46") (name "Net-(U1-VC3)") (class "Default")
      (node (ref "C17") (pin "1") (pinfunction "1_1") (pintype "passive"))
      (node (ref "C18") (pin "2") (pinfunction "2_2") (pintype "passive"))
      (node (ref "R28") (pin "2") (pinfunction "2_2") (pintype "passive"))
      (node (ref "R29") (pin "2") (pinfunction "2_2") (pintype "passive"))
      (node (ref "U1") (pin "24") (pinfunction "VC3_24") (pintype "input"))
    )
    (net (code "47") (name "Net-(U1-VC4)") (class "Default")
      (node (ref "C15") (pin "1") (pinfunction "1_1") (pintype "passive"))
      (node (ref "C17") (pin "2") (pinfunction "2_2") (pintype "passive"))
      (node (ref "R23") (pin "2") (pinfunction "2_2") (pintype "passive"))
      (node (ref "R25") (pin "2") (pinfunction "2_2") (pintype "passive"))
      (node (ref "U1") (pin "23") (pinfunction "VC4_23") (pintype "input"))
    )
    (net (code "48") (name "Net-(U1-VC5B)") (class "Default")
      (node (ref "C11") (pin "2") (pinfunction "2_2") (pintype "passive"))
      (node (ref "R16") (pin "2") (pinfunction "2_2") (pintype "passive"))
      (node (ref "R17") (pin "2") (pinfunction "2_2") (pintype "passive"))
      (node (ref "U1") (pin "21") (pinfunction "VC5B_21") (pintype "input"))
    )
    (net (code "49") (name "Net-(U1-VC6)") (class "Default")
      (node (ref "C5") (pin "1") (pinfunction "1_1") (pintype "passive"))
      (node (ref "C8") (pin "2") (pinfunction "2_2") (pintype "passive"))
      (node (ref "R13") (pin "2") (pinfunction "2_2") (pintype "passive"))
      (node (ref "R14") (pin "2") (pinfunction "2_2") (pintype "passive"))
      (node (ref "U1") (pin "20") (pinfunction "VC6_20") (pintype "input"))
    )
    (net (code "50") (name "Net-(U1-VC7)") (class "Default")
      (node (ref "C2") (pin "1") (pinfunction "1_1") (pintype "passive"))
      (node (ref "C5") (pin "2") (pinfunction "2_2") (pintype "passive"))
      (node (ref "R10") (pin "2") (pinfunction "2_2") (pintype "passive"))
      (node (ref "R8") (pin "2") (pinfunction "2_2") (pintype "passive"))
      (node (ref "U1") (pin "19") (pinfunction "VC7_19") (pintype "input"))
    )
    (net (code "51") (name "Net-(U1-VC8)") (class "Default")
      (node (ref "C1") (pin "1") (pinfunction "1_1") (pintype "passive"))
      (node (ref "C2") (pin "2") (pinfunction "2_2") (pintype "passive"))
      (node (ref "R3") (pin "2") (pinfunction "2_2") (pintype "passive"))
      (node (ref "R6") (pin "2") (pinfunction "2_2") (pintype "passive"))
      (node (ref "U1") (pin "17") (pinfunction "VC9_17") (pintype "input"))
      (node (ref "U1") (pin "18") (pinfunction "VC8_18") (pintype "input"))
    )
    (net (code "52") (name "REGOUT") (class "Default")
      (node (ref "C12") (pin "2") (pinfunction "2_2") (pintype "passive"))
      (node (ref "R21") (pin "2") (pinfunction "2_2") (pintype "passive"))
      (node (ref "R22") (pin "2") (pinfunction "2_2") (pintype "passive"))
      (node (ref "U1") (pin "8") (pinfunction "REGOUT_8") (pintype "passive"))
    )
    (net (code "53") (name "REGSRC") (class "Default")
      (node (ref "C7") (pin "1") (pinfunction "1_1") (pintype "passive"))
      (node (ref "Q3") (pin "2") (pinfunction "Source_2") (pintype "passive"))
      (node (ref "U1") (pin "9") (pinfunction "REGSRC_9") (pintype "passive"))
    )
    (net (code "54") (name "SCL") (class "Default")
      (node (ref "R22") (pin "1") (pinfunction "1_1") (pintype "passive"))
      (node (ref "U1") (pin "5") (pinfunction "SCL_5") (pintype "bidirectional"))
    )
    (net (code "55") (name "SDA") (class "Default")
      (node (ref "R21") (pin "1") (pinfunction "1_1") (pintype "passive"))
      (node (ref "U1") (pin "4") (pinfunction "SDA_4") (pintype "bidirectional"))
    )
    (net (code "56") (name "SRN") (class "Default")
      (node (ref "U1") (pin "29") (pinfunction "SRN_29") (pintype "input"))
    )
    (net (code "57") (name "SRP") (class "Default")
      (node (ref "U1") (pin "28") (pinfunction "SRP_28") (pintype "input"))
    )
    (net (code "58") (name "VC5X") (class "Default")
      (node (ref "C10") (pin "1") (pinfunction "1_1") (pintype "passive"))
      (node (ref "C11") (pin "1") (pinfunction "1_1") (pintype "passive"))
      (node (ref "C3") (pin "1") (pinfunction "1_1") (pintype "passive"))
      (node (ref "C6") (pin "2") (pinfunction "2_2") (pintype "passive"))
      (node (ref "C8") (pin "1") (pinfunction "1_1") (pintype "passive"))
      (node (ref "C9") (pin "1") (pinfunction "1_1") (pintype "passive"))
      (node (ref "D3") (pin "2") (pinfunction "K_2") (pintype "passive"))
      (node (ref "R11") (pin "2") (pinfunction "2_2") (pintype "passive"))
      (node (ref "R18") (pin "2") (pinfunction "2_2") (pintype "passive"))
      (node (ref "RT1") (pin "1") (pinfunction "1_1") (pintype "passive"))
      (node (ref "U1") (pin "10") (pinfunction "VC5X_10") (pintype "input"))
    )
    (net (code "59") (name "VC10X") (class "Default")
      (node (ref "C3") (pin "2") (pinfunction "2_2") (pintype "passive"))
      (node (ref "D5") (pin "2") (pinfunction "K_2") (pintype "passive"))
      (node (ref "R4") (pin "1") (pinfunction "1_1") (pintype "passive"))
      (node (ref "U1") (pin "15") (pinfunction "BAT_15") (pintype "passive"))
    )
    (net (code "60") (name "unconnected-(P1-PadMP1)") (class "Default")
      (node (ref "P1") (pin "MP1") (pinfunction "MP1_MP1") (pintype "passive"))
    )
    (net (code "61") (name "unconnected-(P1-PadMP2)") (class "Default")
      (node (ref "P1") (pin "MP2") (pinfunction "MP2_MP2") (pintype "passive"))
    )
  )
)
